# CANTransceiver.net
KiCad netlist of a schematic drawn in Altium Designer
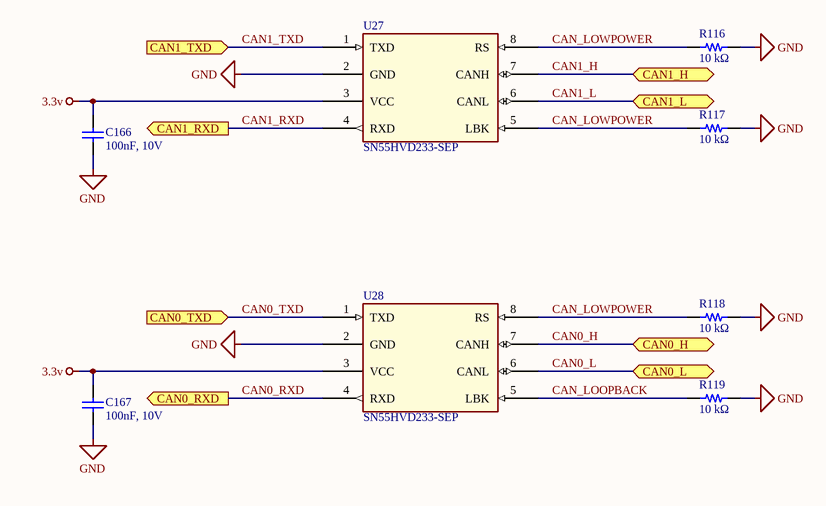
[diagram p0: CANTransceiver.SchDoc]

(export (version "E")
  (design (tool "Eeschema 10.0.6"))
  (components
    (comp (ref "C166")
      (value "100nF, 10V")
      (footprint "WURTH_WCAP-CSGP_0402")
      (description "WCAP-CSGP Multilayer Ceramic Chip Capacitor, General Purpose, size 0402, X7R, 100nF, 10V")
      (fields
        (field (name "MANUFACTURER PART NUMBER") "885012205018")
        (field (name "MANUFACTURER") "Wurth Elektronik")
      )
      (libsource (lib "SpaceVNXBaseBoard") (part "885012205018"))
    )
    (comp (ref "C167")
      (value "100nF, 10V")
      (footprint "WURTH_WCAP-CSGP_0402")
      (description "WCAP-CSGP Multilayer Ceramic Chip Capacitor, General Purpose, size 0402, X7R, 100nF, 10V")
      (fields
        (field (name "MANUFACTURER PART NUMBER") "885012205018")
        (field (name "MANUFACTURER") "Wurth Elektronik")
      )
      (libsource (lib "SpaceVNXBaseBoard") (part "885012205018"))
    )
    (comp (ref "R116")
      (value "10 kΩ")
      (footprint "PANASONIC_ERJ2G_0402")
      (description "General Purpose Thick Film Chip Resistors")
      (fields (field (name "MANUFACTURER") "Panasonic"))
      (libsource (lib "SpaceVNXBaseBoard") (part "ERJ2RKF1002X"))
    )
    (comp (ref "R117")
      (value "10 kΩ")
      (footprint "PANASONIC_ERJ2G_0402")
      (description "General Purpose Thick Film Chip Resistors")
      (fields (field (name "MANUFACTURER") "Panasonic"))
      (libsource (lib "SpaceVNXBaseBoard") (part "ERJ2RKF1002X"))
    )
    (comp (ref "R118")
      (value "10 kΩ")
      (footprint "PANASONIC_ERJ2G_0402")
      (description "General Purpose Thick Film Chip Resistors")
      (fields (field (name "MANUFACTURER") "Panasonic"))
      (libsource (lib "SpaceVNXBaseBoard") (part "ERJ2RKF1002X"))
    )
    (comp (ref "R119")
      (value "10 kΩ")
      (footprint "PANASONIC_ERJ2G_0402")
      (description "General Purpose Thick Film Chip Resistors")
      (fields (field (name "MANUFACTURER") "Panasonic"))
      (libsource (lib "SpaceVNXBaseBoard") (part "ERJ2RKF1002X"))
    )
    (comp (ref "U27")
      (value "SN55HVD233-SEP")
      (footprint "TEXAS_SOIC8D")
      (description "Radiation hardened 3.3V CAN transceiver in space enhanced plastic package with standby mode")
      (libsource (lib "SpaceVNXBaseBoard") (part "SN55HVD233-SEP"))
    )
    (comp (ref "U28")
      (value "SN55HVD233-SEP")
      (footprint "TEXAS_SOIC8D")
      (description "Radiation hardened 3.3V CAN transceiver in space enhanced plastic package with standby mode")
      (libsource (lib "SpaceVNXBaseBoard") (part "SN55HVD233-SEP"))
    )
  )
  (nets
    (net (code "1") (name "/CAN0_H") (class "Default")
      (node (ref "U28") (pin "7") (pinfunction "CANH_7") (pintype "bidirectional"))
    )
    (net (code "2") (name "/CAN0_L") (class "Default")
      (node (ref "U28") (pin "6") (pinfunction "CANL_6") (pintype "bidirectional"))
    )
    (net (code "3") (name "/CAN0_RXD") (class "Default")
      (node (ref "U28") (pin "4") (pinfunction "RXD_4") (pintype "output"))
    )
    (net (code "4") (name "/CAN0_TXD") (class "Default")
      (node (ref "U28") (pin "1") (pinfunction "TXD_1") (pintype "input"))
    )
    (net (code "5") (name "/CAN1_H") (class "Default")
      (node (ref "U27") (pin "7") (pinfunction "CANH_7") (pintype "bidirectional"))
    )
    (net (code "6") (name "/CAN1_L") (class "Default")
      (node (ref "U27") (pin "6") (pinfunction "CANL_6") (pintype "bidirectional"))
    )
    (net (code "7") (name "/CAN1_RXD") (class "Default")
      (node (ref "U27") (pin "4") (pinfunction "RXD_4") (pintype "output"))
    )
    (net (code "8") (name "/CAN1_TXD") (class "Default")
      (node (ref "U27") (pin "1") (pinfunction "TXD_1") (pintype "input"))
    )
    (net (code "9") (name "/CAN_LOOPBACK") (class "Default")
      (node (ref "R119") (pin "1") (pinfunction "1_1") (pintype "passive"))
      (node (ref "U28") (pin "5") (pinfunction "LBK_5") (pintype "input"))
    )
    (net (code "10") (name "/CAN_LOWPOWER") (class "Default")
      (node (ref "R116") (pin "1") (pinfunction "1_1") (pintype "passive"))
      (node (ref "R117") (pin "1") (pinfunction "1_1") (pintype "passive"))
      (node (ref "R118") (pin "1") (pinfunction "1_1") (pintype "passive"))
      (node (ref "U27") (pin "5") (pinfunction "LBK_5") (pintype "input"))
      (node (ref "U27") (pin "8") (pinfunction "RS_8") (pintype "input"))
      (node (ref "U28") (pin "8") (pinfunction "RS_8") (pintype "input"))
    )
    (net (code "11") (name "3.3v") (class "Default")
      (node (ref "C166") (pin "2") (pinfunction "2_2") (pintype "passive"))
      (node (ref "C167") (pin "2") (pinfunction "2_2") (pintype "passive"))
      (node (ref "U27") (pin "3") (pinfunction "VCC_3") (pintype "power_in"))
      (node (ref "U28") (pin "3") (pinfunction "VCC_3") (pintype "power_in"))
    )
    (net (code "12") (name "GND") (class "Default")
      (node (ref "C166") (pin "1") (pinfunction "1_1") (pintype "passive"))
      (node (ref "C167") (pin "1") (pinfunction "1_1") (pintype "passive"))
      (node (ref "R116") (pin "2") (pinfunction "2_2") (pintype "passive"))
      (node (ref "R117") (pin "2") (pinfunction "2_2") (pintype "passive"))
      (node (ref "R118") (pin "2") (pinfunction "2_2") (pintype "passive"))
      (node (ref "R119") (pin "2") (pinfunction "2_2") (pintype "passive"))
      (node (ref "U27") (pin "2") (pinfunction "GND_2") (pintype "passive"))
      (node (ref "U28") (pin "2") (pinfunction "GND_2") (pintype "passive"))
    )
  )
)
